# DEC8L-buscon.net
KiCad netlist of a schematic drawn in EAGLE
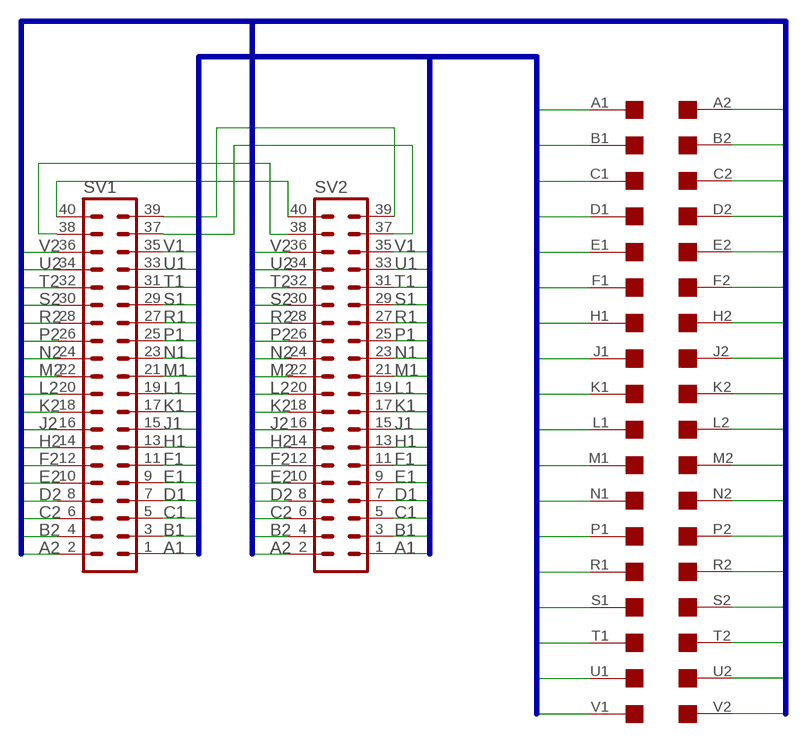
[diagram p0: schematic, sheet 1]

(export (version "E")
  (design (tool "Eeschema 10.0.6"))
  (components
    (comp (ref "SV1")
      (value "MA20-2W")
      (footprint "eagle-import:MA20-2W")
      (libsource (lib "eagle-import") (part "MA20-2W"))
    )
    (comp (ref "SV2")
      (value "MA20-2W")
      (footprint "eagle-import:MA20-2W")
      (libsource (lib "eagle-import") (part "MA20-2W"))
    )
    (comp (ref "U$1")
      (value "DEC-FLIPCHIP")
      (footprint "eagle-import:DEC-FLIPCHIP")
      (libsource (lib "eagle-import") (part "DEC-FLIPCHIP"))
    )
  )
  (nets
    (net (code "1") (name "/A1") (class "Default")
      (node (ref "SV1") (pin "1") (pinfunction "1_1") (pintype "passive"))
      (node (ref "SV2") (pin "1") (pinfunction "1_1") (pintype "passive"))
      (node (ref "U$1") (pin "A1") (pinfunction "A1_A1") (pintype "passive"))
    )
    (net (code "2") (name "/A2") (class "Default")
      (node (ref "SV1") (pin "2") (pinfunction "2_2") (pintype "passive"))
      (node (ref "SV2") (pin "2") (pinfunction "2_2") (pintype "passive"))
      (node (ref "U$1") (pin "A2") (pinfunction "A2_A2") (pintype "passive"))
    )
    (net (code "3") (name "/B1") (class "Default")
      (node (ref "SV1") (pin "3") (pinfunction "3_3") (pintype "passive"))
      (node (ref "SV2") (pin "3") (pinfunction "3_3") (pintype "passive"))
      (node (ref "U$1") (pin "B1") (pinfunction "B1_B1") (pintype "passive"))
    )
    (net (code "4") (name "/B2") (class "Default")
      (node (ref "SV1") (pin "4") (pinfunction "4_4") (pintype "passive"))
      (node (ref "SV2") (pin "4") (pinfunction "4_4") (pintype "passive"))
      (node (ref "U$1") (pin "B2") (pinfunction "B2_B2") (pintype "passive"))
    )
    (net (code "5") (name "/C1") (class "Default")
      (node (ref "SV1") (pin "5") (pinfunction "5_5") (pintype "passive"))
      (node (ref "SV2") (pin "5") (pinfunction "5_5") (pintype "passive"))
      (node (ref "U$1") (pin "C1") (pinfunction "C1_C1") (pintype "passive"))
    )
    (net (code "6") (name "/C2") (class "Default")
      (node (ref "SV1") (pin "6") (pinfunction "6_6") (pintype "passive"))
      (node (ref "SV2") (pin "6") (pinfunction "6_6") (pintype "passive"))
      (node (ref "U$1") (pin "C2") (pinfunction "C2_C2") (pintype "passive"))
    )
    (net (code "7") (name "/D1") (class "Default")
      (node (ref "SV1") (pin "7") (pinfunction "7_7") (pintype "passive"))
      (node (ref "SV2") (pin "7") (pinfunction "7_7") (pintype "passive"))
      (node (ref "U$1") (pin "D1") (pinfunction "D1_D1") (pintype "passive"))
    )
    (net (code "8") (name "/D2") (class "Default")
      (node (ref "SV1") (pin "8") (pinfunction "8_8") (pintype "passive"))
      (node (ref "SV2") (pin "8") (pinfunction "8_8") (pintype "passive"))
      (node (ref "U$1") (pin "D2") (pinfunction "D2_D2") (pintype "passive"))
    )
    (net (code "9") (name "/E1") (class "Default")
      (node (ref "SV1") (pin "9") (pinfunction "9_9") (pintype "passive"))
      (node (ref "SV2") (pin "9") (pinfunction "9_9") (pintype "passive"))
      (node (ref "U$1") (pin "E1") (pinfunction "E1_E1") (pintype "passive"))
    )
    (net (code "10") (name "/E2") (class "Default")
      (node (ref "SV1") (pin "10") (pinfunction "10_10") (pintype "passive"))
      (node (ref "SV2") (pin "10") (pinfunction "10_10") (pintype "passive"))
      (node (ref "U$1") (pin "E2") (pinfunction "E2_E2") (pintype "passive"))
    )
    (net (code "11") (name "/F1") (class "Default")
      (node (ref "SV1") (pin "11") (pinfunction "11_11") (pintype "passive"))
      (node (ref "SV2") (pin "11") (pinfunction "11_11") (pintype "passive"))
      (node (ref "U$1") (pin "F1") (pinfunction "F1_F1") (pintype "passive"))
    )
    (net (code "12") (name "/F2") (class "Default")
      (node (ref "SV1") (pin "12") (pinfunction "12_12") (pintype "passive"))
      (node (ref "SV2") (pin "12") (pinfunction "12_12") (pintype "passive"))
      (node (ref "U$1") (pin "F2") (pinfunction "F2_F2") (pintype "passive"))
    )
    (net (code "13") (name "/H1") (class "Default")
      (node (ref "SV1") (pin "13") (pinfunction "13_13") (pintype "passive"))
      (node (ref "SV2") (pin "13") (pinfunction "13_13") (pintype "passive"))
      (node (ref "U$1") (pin "H1") (pinfunction "H1_H1") (pintype "passive"))
    )
    (net (code "14") (name "/H2") (class "Default")
      (node (ref "SV1") (pin "14") (pinfunction "14_14") (pintype "passive"))
      (node (ref "SV2") (pin "14") (pinfunction "14_14") (pintype "passive"))
      (node (ref "U$1") (pin "H2") (pinfunction "H2_H2") (pintype "passive"))
    )
    (net (code "15") (name "/J1") (class "Default")
      (node (ref "SV1") (pin "15") (pinfunction "15_15") (pintype "passive"))
      (node (ref "SV2") (pin "15") (pinfunction "15_15") (pintype "passive"))
      (node (ref "U$1") (pin "J1") (pinfunction "J1_J1") (pintype "passive"))
    )
    (net (code "16") (name "/J2") (class "Default")
      (node (ref "SV1") (pin "16") (pinfunction "16_16") (pintype "passive"))
      (node (ref "SV2") (pin "16") (pinfunction "16_16") (pintype "passive"))
      (node (ref "U$1") (pin "J2") (pinfunction "J2_J2") (pintype "passive"))
    )
    (net (code "17") (name "/K1") (class "Default")
      (node (ref "SV1") (pin "17") (pinfunction "17_17") (pintype "passive"))
      (node (ref "SV2") (pin "17") (pinfunction "17_17") (pintype "passive"))
      (node (ref "U$1") (pin "K1") (pinfunction "K1_K1") (pintype "passive"))
    )
    (net (code "18") (name "/K2") (class "Default")
      (node (ref "SV1") (pin "18") (pinfunction "18_18") (pintype "passive"))
      (node (ref "SV2") (pin "18") (pinfunction "18_18") (pintype "passive"))
      (node (ref "U$1") (pin "K2") (pinfunction "K2_K2") (pintype "passive"))
    )
    (net (code "19") (name "/L1") (class "Default")
      (node (ref "SV1") (pin "19") (pinfunction "19_19") (pintype "passive"))
      (node (ref "SV2") (pin "19") (pinfunction "19_19") (pintype "passive"))
      (node (ref "U$1") (pin "L1") (pinfunction "L1_L1") (pintype "passive"))
    )
    (net (code "20") (name "/L2") (class "Default")
      (node (ref "SV1") (pin "20") (pinfunction "20_20") (pintype "passive"))
      (node (ref "SV2") (pin "20") (pinfunction "20_20") (pintype "passive"))
      (node (ref "U$1") (pin "L2") (pinfunction "L2_L2") (pintype "passive"))
    )
    (net (code "21") (name "/M1") (class "Default")
      (node (ref "SV1") (pin "21") (pinfunction "21_21") (pintype "passive"))
      (node (ref "SV2") (pin "21") (pinfunction "21_21") (pintype "passive"))
      (node (ref "U$1") (pin "M1") (pinfunction "M1_M1") (pintype "passive"))
    )
    (net (code "22") (name "/M2") (class "Default")
      (node (ref "SV1") (pin "22") (pinfunction "22_22") (pintype "passive"))
      (node (ref "SV2") (pin "22") (pinfunction "22_22") (pintype "passive"))
      (node (ref "U$1") (pin "M2") (pinfunction "M2_M2") (pintype "passive"))
    )
    (net (code "23") (name "/N1") (class "Default")
      (node (ref "SV1") (pin "23") (pinfunction "23_23") (pintype "passive"))
      (node (ref "SV2") (pin "23") (pinfunction "23_23") (pintype "passive"))
      (node (ref "U$1") (pin "N1") (pinfunction "N1_N1") (pintype "passive"))
    )
    (net (code "24") (name "/N2") (class "Default")
      (node (ref "SV1") (pin "24") (pinfunction "24_24") (pintype "passive"))
      (node (ref "SV2") (pin "24") (pinfunction "24_24") (pintype "passive"))
      (node (ref "U$1") (pin "N2") (pinfunction "N2_N2") (pintype "passive"))
    )
    (net (code "25") (name "/P1") (class "Default")
      (node (ref "SV1") (pin "25") (pinfunction "25_25") (pintype "passive"))
      (node (ref "SV2") (pin "25") (pinfunction "25_25") (pintype "passive"))
      (node (ref "U$1") (pin "P1") (pinfunction "P1_P1") (pintype "passive"))
    )
    (net (code "26") (name "/P2") (class "Default")
      (node (ref "SV1") (pin "26") (pinfunction "26_26") (pintype "passive"))
      (node (ref "SV2") (pin "26") (pinfunction "26_26") (pintype "passive"))
      (node (ref "U$1") (pin "P2") (pinfunction "P2_P2") (pintype "passive"))
    )
    (net (code "27") (name "/R1") (class "Default")
      (node (ref "SV1") (pin "27") (pinfunction "27_27") (pintype "passive"))
      (node (ref "SV2") (pin "27") (pinfunction "27_27") (pintype "passive"))
      (node (ref "U$1") (pin "R1") (pinfunction "R1_R1") (pintype "passive"))
    )
    (net (code "28") (name "/R2") (class "Default")
      (node (ref "SV1") (pin "28") (pinfunction "28_28") (pintype "passive"))
      (node (ref "SV2") (pin "28") (pinfunction "28_28") (pintype "passive"))
      (node (ref "U$1") (pin "R2") (pinfunction "R2_R2") (pintype "passive"))
    )
    (net (code "29") (name "/S1") (class "Default")
      (node (ref "SV1") (pin "29") (pinfunction "29_29") (pintype "passive"))
      (node (ref "SV2") (pin "29") (pinfunction "29_29") (pintype "passive"))
      (node (ref "U$1") (pin "S1") (pinfunction "S1_S1") (pintype "passive"))
    )
    (net (code "30") (name "/S2") (class "Default")
      (node (ref "SV1") (pin "30") (pinfunction "30_30") (pintype "passive"))
      (node (ref "SV2") (pin "30") (pinfunction "30_30") (pintype "passive"))
      (node (ref "U$1") (pin "S2") (pinfunction "S2_S2") (pintype "passive"))
    )
    (net (code "31") (name "/T1") (class "Default")
      (node (ref "SV1") (pin "31") (pinfunction "31_31") (pintype "passive"))
      (node (ref "SV2") (pin "31") (pinfunction "31_31") (pintype "passive"))
      (node (ref "U$1") (pin "T1") (pinfunction "T1_T1") (pintype "passive"))
    )
    (net (code "32") (name "/T2") (class "Default")
      (node (ref "SV1") (pin "32") (pinfunction "32_32") (pintype "passive"))
      (node (ref "SV2") (pin "32") (pinfunction "32_32") (pintype "passive"))
      (node (ref "U$1") (pin "T2") (pinfunction "T2_T2") (pintype "passive"))
    )
    (net (code "33") (name "/U1") (class "Default")
      (node (ref "SV1") (pin "33") (pinfunction "33_33") (pintype "passive"))
      (node (ref "SV2") (pin "33") (pinfunction "33_33") (pintype "passive"))
      (node (ref "U$1") (pin "U1") (pinfunction "U1_U1") (pintype "passive"))
    )
    (net (code "34") (name "/U2") (class "Default")
      (node (ref "SV1") (pin "34") (pinfunction "34_34") (pintype "passive"))
      (node (ref "SV2") (pin "34") (pinfunction "34_34") (pintype "passive"))
      (node (ref "U$1") (pin "U2") (pinfunction "U2_U2") (pintype "passive"))
    )
    (net (code "35") (name "/V1") (class "Default")
      (node (ref "SV1") (pin "35") (pinfunction "35_35") (pintype "passive"))
      (node (ref "SV2") (pin "35") (pinfunction "35_35") (pintype "passive"))
      (node (ref "U$1") (pin "V1") (pinfunction "V1_V1") (pintype "passive"))
    )
    (net (code "36") (name "/V2") (class "Default")
      (node (ref "SV1") (pin "36") (pinfunction "36_36") (pintype "passive"))
      (node (ref "SV2") (pin "36") (pinfunction "36_36") (pintype "passive"))
      (node (ref "U$1") (pin "V2") (pinfunction "V2_V2") (pintype "passive"))
    )
    (net (code "37") (name "Net-(SV1-Pad37)") (class "Default")
      (node (ref "SV1") (pin "37") (pinfunction "37_37") (pintype "passive"))
      (node (ref "SV2") (pin "37") (pinfunction "37_37") (pintype "passive"))
    )
    (net (code "38") (name "Net-(SV1-Pad38)") (class "Default")
      (node (ref "SV1") (pin "38") (pinfunction "38_38") (pintype "passive"))
      (node (ref "SV2") (pin "38") (pinfunction "38_38") (pintype "passive"))
    )
    (net (code "39") (name "Net-(SV1-Pad39)") (class "Default")
      (node (ref "SV1") (pin "39") (pinfunction "39_39") (pintype "passive"))
      (node (ref "SV2") (pin "39") (pinfunction "39_39") (pintype "passive"))
    )
    (net (code "40") (name "Net-(SV1-Pad40)") (class "Default")
      (node (ref "SV1") (pin "40") (pinfunction "40_40") (pintype "passive"))
      (node (ref "SV2") (pin "40") (pinfunction "40_40") (pintype "passive"))
    )
  )
)
